# Puissance.net
KiCad netlist of a schematic drawn in Altium Designer
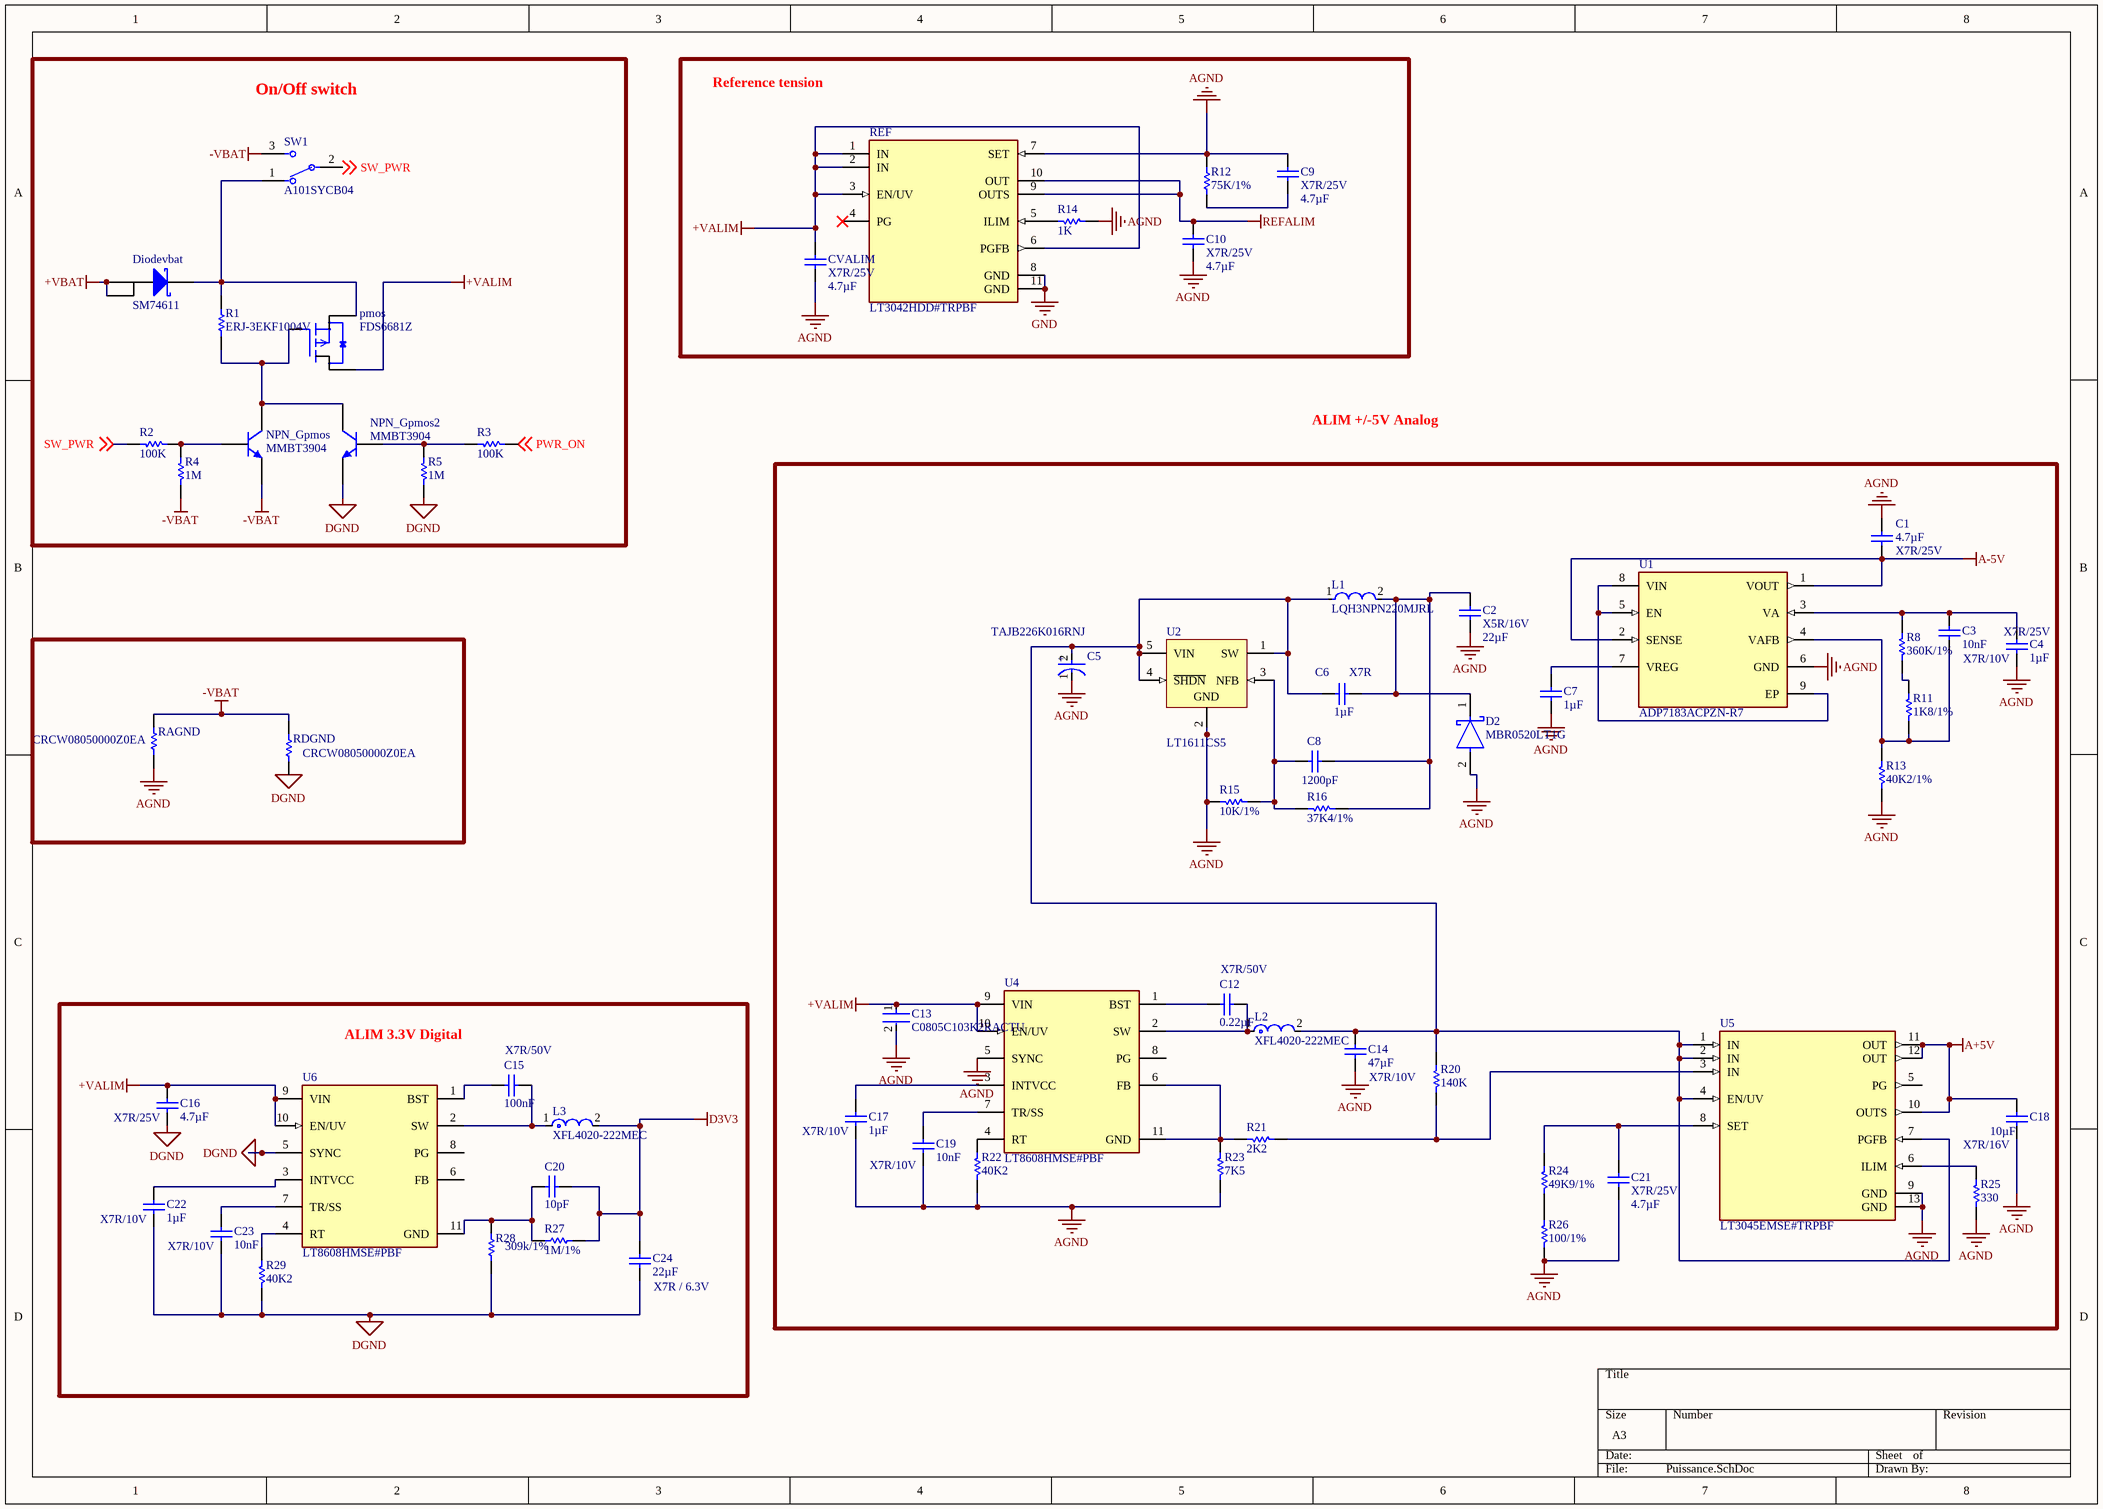
[diagram p0: Puissance.SchDoc]

(export (version "E")
  (design (tool "Eeschema 10.0.6"))
  (components
    (comp (ref "C1")
      (value "X7R/25V")
      (footprint "C1206")
      (description "Capacitor (Semiconductor SIM Model)")
      (fields (field (name "ALTIUM_VALUE") "4.7µF") (field (name "PUBLISHER") "Altium Limited"))
      (libsource (lib "Miscellaneous Devices") (part "Cap Semi"))
    )
    (comp (ref "C2")
      (value "X5R/16V")
      (footprint "C1210")
      (description "Capacitor (Semiconductor SIM Model)")
      (fields (field (name "ALTIUM_VALUE") "22µF") (field (name "PUBLISHER") "Altium Limited"))
      (libsource (lib "Miscellaneous Devices") (part "Cap Semi"))
    )
    (comp (ref "C3")
      (value "X7R/10V")
      (footprint "1608[0603]")
      (description "Capacitor (Semiconductor SIM Model)")
      (fields (field (name "ALTIUM_VALUE") "10nF") (field (name "PUBLISHER") "Altium Limited"))
      (libsource (lib "Miscellaneous Devices") (part "Cap Semi"))
    )
    (comp (ref "C4")
      (value "X7R/25V")
      (footprint "C0805")
      (description "Capacitor (Semiconductor SIM Model)")
      (fields (field (name "ALTIUM_VALUE") "1µF") (field (name "PUBLISHER") "Altium Limited"))
      (libsource (lib "Miscellaneous Devices") (part "Cap Semi"))
    )
    (comp (ref "C5")
      (value "TAJB226K016RNJ")
      (footprint "FP-TAJB-MFG")
      (description "22uF 16V  ±10% 2.3Ω 1210  SMD Tantalum Capacitor")
      (fields (field (name "VOLTAGE") "16V") (field (name "TOLERANCE") "10%"))
      (libsource (lib "Altium Content Vault") (part "203bc49f2ac43e59fd269a8c329ed05"))
    )
    (comp (ref "C6")
      (value "X7R")
      (footprint "C0805")
      (description "Capacitor (Semiconductor SIM Model)")
      (fields (field (name "ALTIUM_VALUE") "1µF") (field (name "PUBLISHER") "Altium Limited"))
      (libsource (lib "Miscellaneous Devices") (part "Cap Semi"))
    )
    (comp (ref "C7")
      (value "1µF")
      (footprint "C0805")
      (description "Capacitor (Semiconductor SIM Model)")
      (fields (field (name "Comment") "X7R/25V") (field (name "PUBLISHER") "Altium Limited"))
      (libsource (lib "Miscellaneous Devices") (part "Cap Semi"))
    )
    (comp (ref "C8")
      (value "1200pF")
      (footprint "1608[0603]")
      (description "Capacitor (Semiconductor SIM Model)")
      (fields (field (name "Comment") "X7R/50V") (field (name "PUBLISHER") "Altium Limited"))
      (libsource (lib "Miscellaneous Devices") (part "Cap Semi"))
    )
    (comp (ref "C9")
      (value "X7R/25V")
      (footprint "C1206")
      (description "Capacitor (Semiconductor SIM Model)")
      (fields (field (name "ALTIUM_VALUE") "4.7µF") (field (name "PUBLISHER") "Altium Limited"))
      (libsource (lib "Miscellaneous Devices") (part "Cap Semi"))
    )
    (comp (ref "C10")
      (value "X7R/25V")
      (footprint "C1206")
      (description "Capacitor (Semiconductor SIM Model)")
      (fields (field (name "ALTIUM_VALUE") "4.7µF") (field (name "PUBLISHER") "Altium Limited"))
      (libsource (lib "Miscellaneous Devices") (part "Cap Semi"))
    )
    (comp (ref "C12")
      (value "X7R/50V")
      (footprint "C0805")
      (description "Capacitor (Semiconductor SIM Model)")
      (fields (field (name "ALTIUM_VALUE") "0.22µF") (field (name "PUBLISHER") "Altium Limited"))
      (libsource (lib "Miscellaneous Devices") (part "Cap Semi"))
    )
    (comp (ref "C13")
      (value "C0805C103K2RACTU")
      (footprint "FP-C0805C-DN-MFG")
      (description "CAP CER 10000PF 200V X7R 0805")
      (fields
        (field (name "OCTOPART") "https://octopart.com/c0805c103k2ractu-kemet-9138347")
        (field (name "TOLERANCE") "0.1")
      )
      (libsource (lib "Altium Content Vault") (part "b4654b650e69147ec39a6b967a45e02"))
    )
    (comp (ref "C14")
      (value "X7R/10V")
      (footprint "C1210")
      (description "Capacitor (Semiconductor SIM Model)")
      (fields (field (name "ALTIUM_VALUE") "47µF") (field (name "PUBLISHER") "Altium Limited"))
      (libsource (lib "Miscellaneous Devices") (part "Cap Semi"))
    )
    (comp (ref "C15")
      (value "X7R/50V")
      (footprint "C0805")
      (description "Capacitor (Semiconductor SIM Model)")
      (fields (field (name "ALTIUM_VALUE") "100nF") (field (name "PUBLISHER") "Altium Limited"))
      (libsource (lib "Miscellaneous Devices") (part "Cap Semi"))
    )
    (comp (ref "C16")
      (value "X7R/25V")
      (footprint "C1206")
      (description "Capacitor (Semiconductor SIM Model)")
      (fields (field (name "ALTIUM_VALUE") "4.7µF") (field (name "PUBLISHER") "Altium Limited"))
      (libsource (lib "Miscellaneous Devices") (part "Cap Semi"))
    )
    (comp (ref "C17")
      (value "X7R/10V")
      (footprint "1608[0603]")
      (description "Capacitor (Semiconductor SIM Model)")
      (fields (field (name "ALTIUM_VALUE") "1µF") (field (name "PUBLISHER") "Altium Limited"))
      (libsource (lib "Miscellaneous Devices") (part "Cap Semi"))
    )
    (comp (ref "C18")
      (value "X7R/16V")
      (footprint "C1206")
      (description "Capacitor (Semiconductor SIM Model)")
      (fields (field (name "ALTIUM_VALUE") "10µF") (field (name "PUBLISHER") "Altium Limited"))
      (libsource (lib "Miscellaneous Devices") (part "Cap Semi"))
    )
    (comp (ref "C19")
      (value "X7R/10V")
      (footprint "1608[0603]")
      (description "Capacitor (Semiconductor SIM Model)")
      (fields (field (name "ALTIUM_VALUE") "10nF") (field (name "PUBLISHER") "Altium Limited"))
      (libsource (lib "Miscellaneous Devices") (part "Cap Semi"))
    )
    (comp (ref "C20")
      (value "10pF")
      (footprint "C0805")
      (description "Capacitor (Semiconductor SIM Model)")
      (fields (field (name "Comment") "Cap Semi") (field (name "PUBLISHER") "Altium Limited"))
      (libsource (lib "Miscellaneous Devices") (part "Cap Semi"))
    )
    (comp (ref "C21")
      (value "X7R/25V")
      (footprint "C1206")
      (description "Capacitor (Semiconductor SIM Model)")
      (fields (field (name "ALTIUM_VALUE") "4.7µF") (field (name "PUBLISHER") "Altium Limited"))
      (libsource (lib "Miscellaneous Devices") (part "Cap Semi"))
    )
    (comp (ref "C22")
      (value "X7R/10V")
      (footprint "1608[0603]")
      (description "Capacitor (Semiconductor SIM Model)")
      (fields (field (name "ALTIUM_VALUE") "1µF") (field (name "PUBLISHER") "Altium Limited"))
      (libsource (lib "Miscellaneous Devices") (part "Cap Semi"))
    )
    (comp (ref "C23")
      (value "X7R/10V")
      (footprint "1608[0603]")
      (description "Capacitor (Semiconductor SIM Model)")
      (fields (field (name "ALTIUM_VALUE") "10nF") (field (name "PUBLISHER") "Altium Limited"))
      (libsource (lib "Miscellaneous Devices") (part "Cap Semi"))
    )
    (comp (ref "C24")
      (value "X7R / 6.3V")
      (footprint "C1210")
      (description "Capacitor (Semiconductor SIM Model)")
      (fields (field (name "ALTIUM_VALUE") "22µF") (field (name "PUBLISHER") "Altium Limited"))
      (libsource (lib "Miscellaneous Devices") (part "Cap Semi"))
    )
    (comp (ref "CVALIM")
      (value "X7R/25V")
      (footprint "C1206")
      (description "Capacitor (Semiconductor SIM Model)")
      (fields (field (name "ALTIUM_VALUE") "4.7µF") (field (name "PUBLISHER") "Altium Limited"))
      (libsource (lib "Miscellaneous Devices") (part "Cap Semi"))
    )
    (comp (ref "D2")
      (value "MBR0520LT1G")
      (footprint "FP-425-04-IPC_C")
      (description "DIODE SCHOTTKY 20V 500MA SOD123")
      (libsource (lib "Altium Content Vault") (part "1d6ec82d83fb6aee721767c19dac4b9"))
    )
    (comp (ref "Diodevbat")
      (value "SM74611")
      (footprint "D2PAK_N")
      (description "Smart Schottky")
      (libsource (lib "Components") (part "SM74611"))
    )
    (comp (ref "L1")
      (value "LQH3NPN220MJRL")
      (footprint "FP-LQH3NPN_JR-MFG")
      (description "Wire Wound Ferrite Inductor for Power Lines 22μH ±20% 0.6Ω 800mA 1212")
      (fields (field (name "TOLERANCE") "20%"))
      (libsource (lib "Altium Content Vault") (part "725321dda6339637d4d059423bc1c3c"))
    )
    (comp (ref "L2")
      (value "XFL4020-222MEC")
      (footprint "FP-XFL4020-MFG")
      (description "INDUCTOR, 2.2UH, 8A, 20%, 38MHZ, REEL")
      (fields (field (name "TOLERANCE") "20%"))
      (libsource (lib "Altium Content Vault") (part "4cc4b267dca4c8e51f7102f422741d8"))
    )
    (comp (ref "L3")
      (value "XFL4020-222MEC")
      (footprint "FP-XFL4020-MFG")
      (description "INDUCTOR, 2.2UH, 8A, 20%, 38MHZ, REEL")
      (fields (field (name "TOLERANCE") "20%"))
      (libsource (lib "Altium Content Vault") (part "4cc4b267dca4c8e51f7102f422741d8"))
    )
    (comp (ref "NPN_Gpmos")
      (value "MMBT3904")
      (footprint "SOT-23_N")
      (description "NPN")
      (libsource (lib "Components") (part "MMBT3904"))
    )
    (comp (ref "NPN_Gpmos2")
      (value "MMBT3904")
      (footprint "SOT-23_N")
      (description "NPN")
      (libsource (lib "Components") (part "MMBT3904"))
    )
    (comp (ref "pmos")
      (value "FDS6681Z")
      (footprint "SO-8")
      (description "P-Channel 30V 20A _Ta_ 2.5W _Ta_ Surface Mount 8-SOIC")
      (fields (field (name "MF") "ON Semiconductor"))
      (libsource (lib "FDS6681Z") (part "FDS6681Z"))
    )
    (comp (ref "R1")
      (value "ERJ-3EKF1004V")
      (footprint "RESC1608X55X30LL15T15")
      (fields (field (name "MANUFACTURER") "Panasonic"))
      (libsource (lib "Altium Content Vault") (part "RES"))
    )
    (comp (ref "R2")
      (value "100K")
      (footprint "0603")
      (description "Resistor")
      (fields (field (name "Comment") "Res CMS") (field (name "PUBLISHER") "Altium Limited"))
      (libsource (lib "Components") (part "Res CMS"))
    )
    (comp (ref "R3")
      (value "100K")
      (footprint "0603")
      (description "Resistor")
      (fields (field (name "Comment") "Res CMS") (field (name "PUBLISHER") "Altium Limited"))
      (libsource (lib "Components") (part "Res CMS"))
    )
    (comp (ref "R4")
      (value "1M")
      (footprint "0603")
      (description "Resistor")
      (fields (field (name "Comment") "Res CMS") (field (name "PUBLISHER") "Altium Limited"))
      (libsource (lib "Components") (part "Res CMS"))
    )
    (comp (ref "R5")
      (value "1M")
      (footprint "0603")
      (description "Resistor")
      (fields (field (name "Comment") "Res CMS") (field (name "PUBLISHER") "Altium Limited"))
      (libsource (lib "Components") (part "Res CMS"))
    )
    (comp (ref "R8")
      (value "360K/1%")
      (footprint "0603")
      (description "Resistor")
      (fields (field (name "PUBLISHER") "Altium Limited"))
      (libsource (lib "Components") (part "Res CMS"))
    )
    (comp (ref "R11")
      (value "1K8/1%")
      (footprint "0603")
      (description "Resistor")
      (fields (field (name "PUBLISHER") "Altium Limited"))
      (libsource (lib "Components") (part "Res CMS"))
    )
    (comp (ref "R12")
      (value "75K/1%")
      (footprint "0603")
      (description "Resistor")
      (fields (field (name "PUBLISHER") "Altium Limited"))
      (libsource (lib "Components") (part "Res CMS"))
    )
    (comp (ref "R13")
      (value "40K2/1%")
      (footprint "0603")
      (description "Resistor")
      (fields (field (name "PUBLISHER") "Altium Limited"))
      (libsource (lib "Components") (part "Res CMS"))
    )
    (comp (ref "R14")
      (value "1K")
      (footprint "0603")
      (description "Resistor")
      (fields (field (name "Comment") "Res CMS") (field (name "PUBLISHER") "Altium Limited"))
      (libsource (lib "Components") (part "Res CMS"))
    )
    (comp (ref "R15")
      (value "10K/1%")
      (footprint "0603")
      (description "Resistor")
      (fields (field (name "PUBLISHER") "Altium Limited"))
      (libsource (lib "Components") (part "Res CMS"))
    )
    (comp (ref "R16")
      (value "37K4/1%")
      (footprint "0603")
      (description "Resistor")
      (fields (field (name "PUBLISHER") "Altium Limited"))
      (libsource (lib "Components") (part "Res CMS"))
    )
    (comp (ref "R20")
      (value "140K")
      (footprint "0603")
      (description "Resistor")
      (fields (field (name "PUBLISHER") "Altium Limited"))
      (libsource (lib "Components") (part "Res CMS"))
    )
    (comp (ref "R21")
      (value "2K2")
      (footprint "0603")
      (description "Resistor")
      (fields (field (name "PUBLISHER") "Altium Limited"))
      (libsource (lib "Components") (part "Res CMS"))
    )
    (comp (ref "R22")
      (value "40K2")
      (footprint "0603")
      (description "Resistor")
      (fields (field (name "PUBLISHER") "Altium Limited"))
      (libsource (lib "Components") (part "Res CMS"))
    )
    (comp (ref "R23")
      (value "7K5")
      (footprint "0603")
      (description "Resistor")
      (fields (field (name "PUBLISHER") "Altium Limited"))
      (libsource (lib "Components") (part "Res CMS"))
    )
    (comp (ref "R24")
      (value "49K9/1%")
      (footprint "0603")
      (description "Resistor")
      (fields (field (name "PUBLISHER") "Altium Limited"))
      (libsource (lib "Components") (part "Res CMS"))
    )
    (comp (ref "R25")
      (value "330")
      (footprint "0603")
      (description "Resistor")
      (fields (field (name "PUBLISHER") "Altium Limited"))
      (libsource (lib "Components") (part "Res CMS"))
    )
    (comp (ref "R26")
      (value "100/1%")
      (footprint "0603")
      (description "Resistor")
      (fields (field (name "PUBLISHER") "Altium Limited"))
      (libsource (lib "Components") (part "Res CMS"))
    )
    (comp (ref "R27")
      (value "1M/1%")
      (footprint "6-0805_M")
      (description "Resistor")
      (fields (field (name "Comment") "Res1") (field (name "PUBLISHER") "Altium Limited"))
      (libsource (lib "Miscellaneous Devices") (part "Res1"))
    )
    (comp (ref "R28")
      (value "309k/1%")
      (footprint "6-0805_M")
      (description "Resistor")
      (fields (field (name "Comment") "Res1") (field (name "PUBLISHER") "Altium Limited"))
      (libsource (lib "Miscellaneous Devices") (part "Res1"))
    )
    (comp (ref "R29")
      (value "40K2")
      (footprint "0603")
      (description "Resistor")
      (fields (field (name "PUBLISHER") "Altium Limited"))
      (libsource (lib "Components") (part "Res CMS"))
    )
    (comp (ref "RAGND")
      (value "CRCW08050000Z0EA")
      (footprint "RESC2013X50X30LL20T20")
      (fields (field (name "MANUFACTURER") "Vishay Dale"))
      (libsource (lib "Altium Content Vault") (part "RES"))
    )
    (comp (ref "RDGND")
      (value "CRCW08050000Z0EA")
      (footprint "RESC2013X50X30LL20T20")
      (fields (field (name "MANUFACTURER") "Vishay Dale"))
      (libsource (lib "Altium Content Vault") (part "RES"))
    )
    (comp (ref "REF")
      (value "LT3042HDD#TRPBF")
      (footprint "FP-DD-10-05-08-1699-IPC_C")
      (description "IC REG LIN POS ADJ 200MA 10DFN")
      (libsource (lib "Altium Content Vault") (part "d4f70c3831b5423a4a5786fde8b37b7"))
    )
    (comp (ref "SW1")
      (value "A101SYCB04")
      (footprint "FP-A101SYCB04-MFG")
      (description "SWITCH TOGGLE SPDT 0.4VA 20V")
      (libsource (lib "Altium Content Vault") (part "52c419afdc2a387c7d548259a9aeefb"))
    )
    (comp (ref "U1")
      (value "ADP7183ACPZN-R7")
      (footprint "FP-CP-8-27-IPC_B")
      (description "IC REG LIN NEG ADJ 300MA 8LFCSP")
      (libsource (lib "Altium Content Vault") (part "f8874ef2df6207003ca0ec43ba25d2c"))
    )
    (comp (ref "U2")
      (value "LT1611CS5")
      (footprint "LT-S5-5-SOT-23_M")
      (description "Inverting 1.4 MHz Switching Regulator, 5-pin SOT23 (S5-5), 0 to 70 degC")
      (fields (field (name "MANUFACTURER") "Linear Technology"))
      (libsource (lib "Altium Content Vault") (part "LT-LT161X_1931-S5-5"))
    )
    (comp (ref "U4")
      (value "LT8608HMSE#PBF")
      (footprint "FP-MSE-10-05-08-1664-IPC_A")
      (description "IC REG BUCK ADJ 1.5A 10MSOP")
      (libsource (lib "Altium Content Vault") (part "d4229aa3123c3aabb632f19deea9d65"))
    )
    (comp (ref "U5")
      (value "LT3045EMSE#TRPBF")
      (footprint "FP-MSE-12-05-08-1666-IPC_B")
      (description "IC REG LINEAR 0V 500MA 12MSOP")
      (libsource (lib "Altium Content Vault") (part "d2cf54c958f747b30b151eff905336d"))
    )
    (comp (ref "U6")
      (value "LT8608HMSE#PBF")
      (footprint "FP-MSE-10-05-08-1664-IPC_A")
      (description "IC REG BUCK ADJ 1.5A 10MSOP")
      (libsource (lib "Altium Content Vault") (part "d4229aa3123c3aabb632f19deea9d65"))
    )
  )
  (nets
    (net (code "1") (name "+VALIM") (class "Default")
      (node (ref "C13") (pin "1") (pinfunction "1_1") (pintype "passive"))
      (node (ref "C16") (pin "2") (pinfunction "2_2") (pintype "passive"))
      (node (ref "CVALIM") (pin "1") (pinfunction "1_1") (pintype "passive"))
      (node (ref "REF") (pin "1") (pinfunction "IN_1") (pintype "power_in"))
      (node (ref "REF") (pin "2") (pinfunction "IN_2") (pintype "power_in"))
      (node (ref "REF") (pin "3") (pinfunction "EN/UV_3") (pintype "input"))
      (node (ref "REF") (pin "6") (pinfunction "PGFB_6") (pintype "output"))
      (node (ref "U4") (pin "10") (pinfunction "EN/UV_10") (pintype "input"))
      (node (ref "U4") (pin "9") (pinfunction "VIN_9") (pintype "power_in"))
      (node (ref "U6") (pin "10") (pinfunction "EN/UV_10") (pintype "input"))
      (node (ref "U6") (pin "9") (pinfunction "VIN_9") (pintype "power_in"))
      (node (ref "pmos") (pin "8") (pinfunction "D@4_8") (pintype "passive"))
    )
    (net (code "2") (name "+VBAT") (class "Default")
      (node (ref "Diodevbat") (pin "1") (pinfunction "A_1") (pintype "passive"))
      (node (ref "Diodevbat") (pin "3") (pinfunction "A_3") (pintype "passive"))
    )
    (net (code "3") (name "-VBAT") (class "Default")
      (node (ref "NPN_Gpmos") (pin "2") (pinfunction "E_2") (pintype "passive"))
      (node (ref "R4") (pin "2") (pinfunction "2_2") (pintype "passive"))
      (node (ref "RAGND") (pin "2") (pinfunction "2_2") (pintype "passive"))
      (node (ref "RDGND") (pin "2") (pinfunction "2_2") (pintype "passive"))
      (node (ref "SW1") (pin "3") (pinfunction "3_3") (pintype "passive"))
    )
    (net (code "4") (name "A+5V") (class "Default")
      (node (ref "C18") (pin "1") (pinfunction "1_1") (pintype "passive"))
      (node (ref "U5") (pin "10") (pinfunction "OUTS_10") (pintype "output"))
      (node (ref "U5") (pin "11") (pinfunction "OUT_11") (pintype "output"))
      (node (ref "U5") (pin "12") (pinfunction "OUT_12") (pintype "output"))
    )
    (net (code "5") (name "A-5V") (class "Default")
      (node (ref "C1") (pin "1") (pinfunction "1_1") (pintype "passive"))
      (node (ref "U1") (pin "1") (pinfunction "VOUT_1") (pintype "output"))
      (node (ref "U1") (pin "2") (pinfunction "SENSE_2") (pintype "input"))
    )
    (net (code "6") (name "AGND") (class "Default")
      (node (ref "C1") (pin "2") (pinfunction "2_2") (pintype "passive"))
      (node (ref "C10") (pin "2") (pinfunction "2_2") (pintype "passive"))
      (node (ref "C13") (pin "2") (pinfunction "2_2") (pintype "passive"))
      (node (ref "C14") (pin "2") (pinfunction "2_2") (pintype "passive"))
      (node (ref "C17") (pin "1") (pinfunction "1_1") (pintype "passive"))
      (node (ref "C18") (pin "2") (pinfunction "2_2") (pintype "passive"))
      (node (ref "C19") (pin "1") (pinfunction "1_1") (pintype "passive"))
      (node (ref "C2") (pin "2") (pinfunction "2_2") (pintype "passive"))
      (node (ref "C21") (pin "1") (pinfunction "1_1") (pintype "passive"))
      (node (ref "C4") (pin "1") (pinfunction "1_1") (pintype "passive"))
      (node (ref "C5") (pin "1") (pinfunction "C_1") (pintype "passive"))
      (node (ref "C7") (pin "1") (pinfunction "1_1") (pintype "passive"))
      (node (ref "C9") (pin "1") (pinfunction "1_1") (pintype "passive"))
      (node (ref "CVALIM") (pin "2") (pinfunction "2_2") (pintype "passive"))
      (node (ref "D2") (pin "2") (pinfunction "A_2") (pintype "passive"))
      (node (ref "R12") (pin "2") (pinfunction "2_2") (pintype "passive"))
      (node (ref "R13") (pin "2") (pinfunction "2_2") (pintype "passive"))
      (node (ref "R14") (pin "2") (pinfunction "2_2") (pintype "passive"))
      (node (ref "R15") (pin "1") (pinfunction "1_1") (pintype "passive"))
      (node (ref "R22") (pin "2") (pinfunction "2_2") (pintype "passive"))
      (node (ref "R23") (pin "2") (pinfunction "2_2") (pintype "passive"))
      (node (ref "R25") (pin "2") (pinfunction "2_2") (pintype "passive"))
      (node (ref "R26") (pin "2") (pinfunction "2_2") (pintype "passive"))
      (node (ref "RAGND") (pin "1") (pinfunction "1_1") (pintype "passive"))
      (node (ref "REF") (pin "7") (pinfunction "SET_7") (pintype "input"))
      (node (ref "U1") (pin "6") (pinfunction "GND_6") (pintype "power_in"))
      (node (ref "U2") (pin "2") (pinfunction "GND_2") (pintype "power_in"))
      (node (ref "U4") (pin "5") (pinfunction "SYNC_5") (pintype "passive"))
      (node (ref "U5") (pin "13") (pinfunction "GND_13") (pintype "power_in"))
      (node (ref "U5") (pin "9") (pinfunction "GND_9") (pintype "power_in"))
    )
    (net (code "7") (name "D3V3") (class "Default")
      (node (ref "C20") (pin "2") (pinfunction "2_2") (pintype "passive"))
      (node (ref "C24") (pin "1") (pinfunction "1_1") (pintype "passive"))
      (node (ref "L3") (pin "2") (pinfunction "2_2") (pintype "passive"))
      (node (ref "R27") (pin "1") (pinfunction "1_1") (pintype "passive"))
    )
    (net (code "8") (name "DGND") (class "Default")
      (node (ref "C16") (pin "1") (pinfunction "1_1") (pintype "passive"))
      (node (ref "C22") (pin "1") (pinfunction "1_1") (pintype "passive"))
      (node (ref "C23") (pin "1") (pinfunction "1_1") (pintype "passive"))
      (node (ref "C24") (pin "2") (pinfunction "2_2") (pintype "passive"))
      (node (ref "NPN_Gpmos2") (pin "2") (pinfunction "E_2") (pintype "passive"))
      (node (ref "R28") (pin "1") (pinfunction "1_1") (pintype "passive"))
      (node (ref "R29") (pin "2") (pinfunction "2_2") (pintype "passive"))
      (node (ref "R5") (pin "2") (pinfunction "2_2") (pintype "passive"))
      (node (ref "U6") (pin "5") (pinfunction "SYNC_5") (pintype "passive"))
    )
    (net (code "9") (name "GND") (class "Default")
      (node (ref "REF") (pin "11") (pinfunction "GND_11") (pintype "power_in"))
      (node (ref "REF") (pin "8") (pinfunction "GND_8") (pintype "power_in"))
    )
    (net (code "10") (name "Net-(C5-A)") (class "Default")
      (node (ref "C14") (pin "1") (pinfunction "1_1") (pintype "passive"))
      (node (ref "C5") (pin "2") (pinfunction "A_2") (pintype "passive"))
      (node (ref "C6") (pin "2") (pinfunction "2_2") (pintype "passive"))
      (node (ref "L1") (pin "1") (pinfunction "1_1") (pintype "passive"))
      (node (ref "L2") (pin "2") (pinfunction "2_2") (pintype "passive"))
      (node (ref "R20") (pin "1") (pinfunction "1_1") (pintype "passive"))
      (node (ref "U2") (pin "1") (pinfunction "SW_1") (pintype "power_in"))
      (node (ref "U2") (pin "4") (pinfunction "~{SHDN}_4") (pintype "input"))
      (node (ref "U2") (pin "5") (pinfunction "VIN_5") (pintype "power_in"))
      (node (ref "U5") (pin "1") (pinfunction "IN_1") (pintype "input"))
      (node (ref "U5") (pin "2") (pinfunction "IN_2") (pintype "input"))
      (node (ref "U5") (pin "4") (pinfunction "EN/UV_4") (pintype "input"))
      (node (ref "U5") (pin "7") (pinfunction "PGFB_7") (pintype "input"))
    )
    (net (code "11") (name "Net-(C9-Pad2)") (class "Default")
      (node (ref "C9") (pin "2") (pinfunction "2_2") (pintype "passive"))
      (node (ref "R12") (pin "1") (pinfunction "1_1") (pintype "passive"))
    )
    (net (code "12") (name "Net-(D2-C)") (class "Default")
      (node (ref "C2") (pin "1") (pinfunction "1_1") (pintype "passive"))
      (node (ref "C6") (pin "1") (pinfunction "1_1") (pintype "passive"))
      (node (ref "C8") (pin "1") (pinfunction "1_1") (pintype "passive"))
      (node (ref "D2") (pin "1") (pinfunction "C_1") (pintype "passive"))
      (node (ref "L1") (pin "2") (pinfunction "2_2") (pintype "passive"))
      (node (ref "R16") (pin "2") (pinfunction "2_2") (pintype "passive"))
    )
    (net (code "13") (name "Net-(Diodevbat-K)") (class "Default")
      (node (ref "Diodevbat") (pin "2") (pinfunction "K_2") (pintype "passive"))
      (node (ref "R1") (pin "2") (pinfunction "2_2") (pintype "passive"))
      (node (ref "SW1") (pin "1") (pinfunction "1_1") (pintype "passive"))
      (node (ref "pmos") (pin "3") (pinfunction "S@3_3") (pintype "passive"))
    )
    (net (code "14") (name "Net-(NPN_Gpmos-B)") (class "Default")
      (node (ref "NPN_Gpmos") (pin "1") (pinfunction "B_1") (pintype "passive"))
      (node (ref "R2") (pin "2") (pinfunction "2_2") (pintype "passive"))
      (node (ref "R4") (pin "1") (pinfunction "1_1") (pintype "passive"))
    )
    (net (code "15") (name "Net-(NPN_Gpmos-C)") (class "Default")
      (node (ref "NPN_Gpmos") (pin "3") (pinfunction "C_3") (pintype "passive"))
      (node (ref "NPN_Gpmos2") (pin "3") (pinfunction "C_3") (pintype "passive"))
      (node (ref "R1") (pin "1") (pinfunction "1_1") (pintype "passive"))
      (node (ref "pmos") (pin "4") (pinfunction "G_4") (pintype "passive"))
    )
    (net (code "16") (name "Net-(NPN_Gpmos2-B)") (class "Default")
      (node (ref "NPN_Gpmos2") (pin "1") (pinfunction "B_1") (pintype "passive"))
      (node (ref "R3") (pin "1") (pinfunction "1_1") (pintype "passive"))
      (node (ref "R5") (pin "1") (pinfunction "1_1") (pintype "passive"))
    )
    (net (code "17") (name "Net-(R11-Pad1)") (class "Default")
      (node (ref "R11") (pin "1") (pinfunction "1_1") (pintype "passive"))
      (node (ref "R8") (pin "2") (pinfunction "2_2") (pintype "passive"))
    )
    (net (code "18") (name "Net-(R20-Pad2)") (class "Default")
      (node (ref "R20") (pin "2") (pinfunction "2_2") (pintype "passive"))
      (node (ref "R21") (pin "2") (pinfunction "2_2") (pintype "passive"))
      (node (ref "U5") (pin "3") (pinfunction "IN_3") (pintype "input"))
    )
    (net (code "19") (name "Net-(R24-Pad2)") (class "Default")
      (node (ref "R24") (pin "2") (pinfunction "2_2") (pintype "passive"))
      (node (ref "R26") (pin "1") (pinfunction "1_1") (pintype "passive"))
    )
    (net (code "20") (name "Net-(REF-ILIM)") (class "Default")
      (node (ref "R14") (pin "1") (pinfunction "1_1") (pintype "passive"))
      (node (ref "REF") (pin "5") (pinfunction "ILIM_5") (pintype "input"))
    )
    (net (code "21") (name "Net-(U1-EN)") (class "Default")
      (node (ref "U1") (pin "5") (pinfunction "EN_5") (pintype "input"))
      (node (ref "U1") (pin "8") (pinfunction "VIN_8") (pintype "power_in"))
      (node (ref "U1") (pin "9") (pinfunction "EP_9") (pintype "power_in"))
    )
    (net (code "22") (name "Net-(U1-VA)") (class "Default")
      (node (ref "C3") (pin "2") (pinfunction "2_2") (pintype "passive"))
      (node (ref "C4") (pin "2") (pinfunction "2_2") (pintype "passive"))
      (node (ref "R8") (pin "1") (pinfunction "1_1") (pintype "passive"))
      (node (ref "U1") (pin "3") (pinfunction "VA_3") (pintype "input"))
    )
    (net (code "23") (name "Net-(U1-VAFB)") (class "Default")
      (node (ref "C3") (pin "1") (pinfunction "1_1") (pintype "passive"))
      (node (ref "R11") (pin "2") (pinfunction "2_2") (pintype "passive"))
      (node (ref "R13") (pin "1") (pinfunction "1_1") (pintype "passive"))
      (node (ref "U1") (pin "4") (pinfunction "VAFB_4") (pintype "output"))
    )
    (net (code "24") (name "Net-(U1-VREG)") (class "Default")
      (node (ref "C7") (pin "2") (pinfunction "2_2") (pintype "passive"))
      (node (ref "U1") (pin "7") (pinfunction "VREG_7") (pintype "power_in"))
    )
    (net (code "25") (name "Net-(U2-NFB)") (class "Default")
      (node (ref "C8") (pin "2") (pinfunction "2_2") (pintype "passive"))
      (node (ref "R15") (pin "2") (pinfunction "2_2") (pintype "passive"))
      (node (ref "R16") (pin "1") (pinfunction "1_1") (pintype "passive"))
      (node (ref "U2") (pin "3") (pinfunction "NFB_3") (pintype "input"))
    )
    (net (code "26") (name "Net-(U4-BST)") (class "Default")
      (node (ref "C12") (pin "1") (pinfunction "1_1") (pintype "passive"))
      (node (ref "U4") (pin "1") (pinfunction "BST_1") (pintype "passive"))
    )
    (net (code "27") (name "Net-(U4-FB)") (class "Default")
      (node (ref "R21") (pin "1") (pinfunction "1_1") (pintype "passive"))
      (node (ref "R23") (pin "1") (pinfunction "1_1") (pintype "passive"))
      (node (ref "U4") (pin "11") (pinfunction "GND_11") (pintype "power_in"))
      (node (ref "U4") (pin "6") (pinfunction "FB_6") (pintype "passive"))
    )
    (net (code "28") (name "Net-(U4-INTVCC)") (class "Default")
      (node (ref "C17") (pin "2") (pinfunction "2_2") (pintype "passive"))
      (node (ref "U4") (pin "3") (pinfunction "INTVCC_3") (pintype "passive"))
    )
    (net (code "29") (name "Net-(U4-RT)") (class "Default")
      (node (ref "R22") (pin "1") (pinfunction "1_1") (pintype "passive"))
      (node (ref "U4") (pin "4") (pinfunction "RT_4") (pintype "passive"))
    )
    (net (code "30") (name "Net-(U4-SW)") (class "Default")
      (node (ref "C12") (pin "2") (pinfunction "2_2") (pintype "passive"))
      (node (ref "L2") (pin "1") (pinfunction "1_1") (pintype "passive"))
      (node (ref "U4") (pin "2") (pinfunction "SW_2") (pintype "passive"))
    )
    (net (code "31") (name "Net-(U4-TR{slash}SS)") (class "Default")
      (node (ref "C19") (pin "2") (pinfunction "2_2") (pintype "passive"))
      (node (ref "U4") (pin "7") (pinfunction "TR/SS_7") (pintype "passive"))
    )
    (net (code "32") (name "Net-(U5-ILIM)") (class "Default")
      (node (ref "R25") (pin "1") (pinfunction "1_1") (pintype "passive"))
      (node (ref "U5") (pin "6") (pinfunction "ILIM_6") (pintype "input"))
    )
    (net (code "33") (name "Net-(U5-SET)") (class "Default")
      (node (ref "C21") (pin "2") (pinfunction "2_2") (pintype "passive"))
      (node (ref "R24") (pin "1") (pinfunction "1_1") (pintype "passive"))
      (node (ref "U5") (pin "8") (pinfunction "SET_8") (pintype "input"))
    )
    (net (code "34") (name "Net-(U6-BST)") (class "Default")
      (node (ref "C15") (pin "1") (pinfunction "1_1") (pintype "passive"))
      (node (ref "U6") (pin "1") (pinfunction "BST_1") (pintype "passive"))
    )
    (net (code "35") (name "Net-(U6-GND)") (class "Default")
      (node (ref "C20") (pin "1") (pinfunction "1_1") (pintype "passive"))
      (node (ref "R27") (pin "2") (pinfunction "2_2") (pintype "passive"))
      (node (ref "R28") (pin "2") (pinfunction "2_2") (pintype "passive"))
      (node (ref "U6") (pin "11") (pinfunction "GND_11") (pintype "power_in"))
    )
    (net (code "36") (name "Net-(U6-INTVCC)") (class "Default")
      (node (ref "C22") (pin "2") (pinfunction "2_2") (pintype "passive"))
      (node (ref "U6") (pin "3") (pinfunction "INTVCC_3") (pintype "passive"))
    )
    (net (code "37") (name "Net-(U6-RT)") (class "Default")
      (node (ref "R29") (pin "1") (pinfunction "1_1") (pintype "passive"))
      (node (ref "U6") (pin "4") (pinfunction "RT_4") (pintype "passive"))
    )
    (net (code "38") (name "Net-(U6-SW)") (class "Default")
      (node (ref "C15") (pin "2") (pinfunction "2_2") (pintype "passive"))
      (node (ref "L3") (pin "1") (pinfunction "1_1") (pintype "passive"))
      (node (ref "U6") (pin "2") (pinfunction "SW_2") (pintype "passive"))
    )
    (net (code "39") (name "Net-(U6-TR{slash}SS)") (class "Default")
      (node (ref "C23") (pin "2") (pinfunction "2_2") (pintype "passive"))
      (node (ref "U6") (pin "7") (pinfunction "TR/SS_7") (pintype "passive"))
    )
    (net (code "40") (name "PWR_ON") (class "Default")
      (node (ref "R3") (pin "2") (pinfunction "2_2") (pintype "passive"))
    )
    (net (code "41") (name "REFALIM") (class "Default")
      (node (ref "C10") (pin "1") (pinfunction "1_1") (pintype "passive"))
      (node (ref "REF") (pin "10") (pinfunction "OUT_10") (pintype "passive"))
      (node (ref "REF") (pin "9") (pinfunction "OUTS_9") (pintype "passive"))
    )
    (net (code "42") (name "SW_PWR") (class "Default")
      (node (ref "R2") (pin "1") (pinfunction "1_1") (pintype "passive"))
      (node (ref "SW1") (pin "2") (pinfunction "2_2") (pintype "passive"))
    )
    (net (code "43") (name "unconnected-(RDGND-Pad1)") (class "Default")
      (node (ref "RDGND") (pin "1") (pinfunction "1_1") (pintype "passive"))
    )
    (net (code "44") (name "unconnected-(REF-PG-Pad4)") (class "Default")
      (node (ref "REF") (pin "4") (pinfunction "PG_4") (pintype "open_collector+no_connect"))
    )
    (net (code "45") (name "unconnected-(U4-PG-Pad8)") (class "Default")
      (node (ref "U4") (pin "8") (pinfunction "PG_8") (pintype "open_collector"))
    )
    (net (code "46") (name "unconnected-(U5-PG-Pad5)") (class "Default")
      (node (ref "U5") (pin "5") (pinfunction "PG_5") (pintype "output"))
    )
    (net (code "47") (name "unconnected-(U6-FB-Pad6)") (class "Default")
      (node (ref "U6") (pin "6") (pinfunction "FB_6") (pintype "passive"))
    )
    (net (code "48") (name "unconnected-(U6-PG-Pad8)") (class "Default")
      (node (ref "U6") (pin "8") (pinfunction "PG_8") (pintype "open_collector"))
    )
    (net (code "49") (name "unconnected-(pmos-D@1-Pad5)") (class "Default")
      (node (ref "pmos") (pin "5") (pinfunction "D@1_5") (pintype "passive"))
    )
    (net (code "50") (name "unconnected-(pmos-D@2-Pad6)") (class "Default")
      (node (ref "pmos") (pin "6") (pinfunction "D@2_6") (pintype "passive"))
    )
    (net (code "51") (name "unconnected-(pmos-D@3-Pad7)") (class "Default")
      (node (ref "pmos") (pin "7") (pinfunction "D@3_7") (pintype "passive"))
    )
    (net (code "52") (name "unconnected-(pmos-S@1-Pad1)") (class "Default")
      (node (ref "pmos") (pin "1") (pinfunction "S@1_1") (pintype "passive"))
    )
    (net (code "53") (name "unconnected-(pmos-S@2-Pad2)") (class "Default")
      (node (ref "pmos") (pin "2") (pinfunction "S@2_2") (pintype "passive"))
    )
  )
)
